# crosstalk-1.net
KiCad netlist of a schematic drawn in Altium Designer
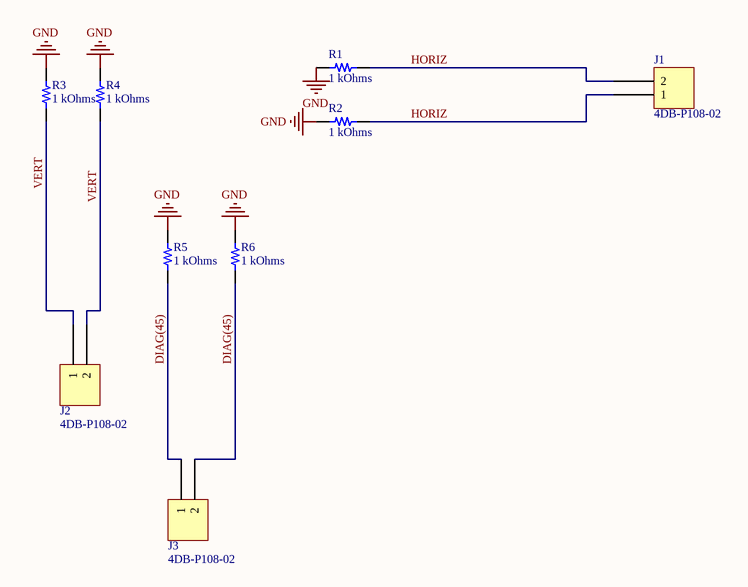
[diagram p0: crosstalk-1.SchDoc]

(export (version "E")
  (design (tool "Eeschema 10.0.6"))
  (components
    (comp (ref "J1")
      (value "4DB-P108-02")
      (footprint "TE 4DB-P108-02")
      (description "CONN BARRIER STRIP 2CIRC 0.325\"")
      (fields (field (name "MANUFACTURER") "TE Connectivity AMP Connectors"))
      (libsource (lib "") (part "2 Pin_1"))
    )
    (comp (ref "J2")
      (value "4DB-P108-02")
      (footprint "TE 4DB-P108-02")
      (description "CONN BARRIER STRIP 2CIRC 0.325\"")
      (fields (field (name "MANUFACTURER") "TE Connectivity AMP Connectors"))
      (libsource (lib "Celestial Altium Library - altium_library") (part "2 Pin"))
    )
    (comp (ref "J3")
      (value "4DB-P108-02")
      (footprint "TE 4DB-P108-02")
      (description "CONN BARRIER STRIP 2CIRC 0.325\"")
      (fields (field (name "MANUFACTURER") "TE Connectivity AMP Connectors"))
      (libsource (lib "Celestial Altium Library - altium_library") (part "2 Pin"))
    )
    (comp (ref "R1")
      (value "1 kOhms")
      (footprint "RES 0603_1608")
      (description "RES SMD 1K OHM 0.1% 1/16W 0603")
      (fields
        (field (name "PART NUMBER") "CPF0603B1K0E")
        (field (name "MANUFACTURER") "TE Connectivity Passive Product")
      )
      (libsource (lib "Celestial Altium Library - altium_library") (part "Resistor"))
    )
    (comp (ref "R2")
      (value "1 kOhms")
      (footprint "RES 0603_1608")
      (description "RES SMD 1K OHM 0.1% 1/16W 0603")
      (fields
        (field (name "PART NUMBER") "CPF0603B1K0E")
        (field (name "MANUFACTURER") "TE Connectivity Passive Product")
      )
      (libsource (lib "Celestial Altium Library - altium_library") (part "Resistor"))
    )
    (comp (ref "R3")
      (value "1 kOhms")
      (footprint "RES 0603_1608")
      (description "RES SMD 1K OHM 0.1% 1/16W 0603")
      (fields
        (field (name "PART NUMBER") "CPF0603B1K0E")
        (field (name "MANUFACTURER") "TE Connectivity Passive Product")
      )
      (libsource (lib "Celestial Altium Library - altium_library") (part "Resistor"))
    )
    (comp (ref "R4")
      (value "1 kOhms")
      (footprint "RES 0603_1608")
      (description "RES SMD 1K OHM 0.1% 1/16W 0603")
      (fields
        (field (name "PART NUMBER") "CPF0603B1K0E")
        (field (name "MANUFACTURER") "TE Connectivity Passive Product")
      )
      (libsource (lib "Celestial Altium Library - altium_library") (part "Resistor"))
    )
    (comp (ref "R5")
      (value "1 kOhms")
      (footprint "RES 0603_1608")
      (description "RES SMD 1K OHM 0.1% 1/16W 0603")
      (fields
        (field (name "PART NUMBER") "CPF0603B1K0E")
        (field (name "MANUFACTURER") "TE Connectivity Passive Product")
      )
      (libsource (lib "Celestial Altium Library - altium_library") (part "Resistor"))
    )
    (comp (ref "R6")
      (value "1 kOhms")
      (footprint "RES 0603_1608")
      (description "RES SMD 1K OHM 0.1% 1/16W 0603")
      (fields
        (field (name "PART NUMBER") "CPF0603B1K0E")
        (field (name "MANUFACTURER") "TE Connectivity Passive Product")
      )
      (libsource (lib "Celestial Altium Library - altium_library") (part "Resistor"))
    )
  )
  (nets
    (net (code "1") (name "/DIAG(45)") (class "Default")
      (node (ref "J3") (pin "1") (pinfunction "1_1") (pintype "passive"))
      (node (ref "J3") (pin "2") (pinfunction "2_2") (pintype "passive"))
      (node (ref "R5") (pin "2") (pinfunction "2_2") (pintype "passive"))
      (node (ref "R6") (pin "2") (pinfunction "2_2") (pintype "passive"))
    )
    (net (code "2") (name "/HORIZ") (class "Default")
      (node (ref "J1") (pin "1") (pinfunction "1_1") (pintype "passive"))
      (node (ref "J1") (pin "2") (pinfunction "2_2") (pintype "passive"))
      (node (ref "R1") (pin "1") (pinfunction "1_1") (pintype "passive"))
      (node (ref "R2") (pin "1") (pinfunction "1_1") (pintype "passive"))
    )
    (net (code "3") (name "/VERT") (class "Default")
      (node (ref "J2") (pin "1") (pinfunction "1_1") (pintype "passive"))
      (node (ref "J2") (pin "2") (pinfunction "2_2") (pintype "passive"))
      (node (ref "R3") (pin "1") (pinfunction "1_1") (pintype "passive"))
      (node (ref "R4") (pin "1") (pinfunction "1_1") (pintype "passive"))
    )
    (net (code "4") (name "GND") (class "Default")
      (node (ref "R1") (pin "2") (pinfunction "2_2") (pintype "passive"))
      (node (ref "R2") (pin "2") (pinfunction "2_2") (pintype "passive"))
      (node (ref "R3") (pin "2") (pinfunction "2_2") (pintype "passive"))
      (node (ref "R4") (pin "2") (pinfunction "2_2") (pintype "passive"))
      (node (ref "R5") (pin "1") (pinfunction "1_1") (pintype "passive"))
      (node (ref "R6") (pin "1") (pinfunction "1_1") (pintype "passive"))
    )
  )
)
